# LED_RED_0603x8.net
KiCad netlist of a schematic drawn in Altium Designer
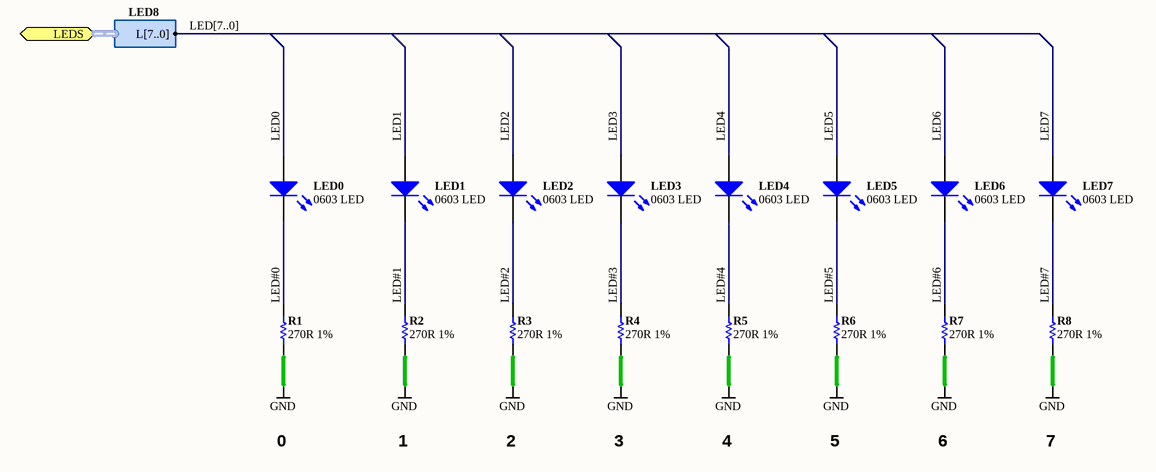
[diagram p0: LED_RED_0603x8.SCHDOC]

(export (version "E")
  (design (tool "Eeschema 10.0.6"))
  (components
    (comp (ref "LED0")
      (value "0603 LED")
      (footprint "0603LED")
      (description "LED, Red 0603 (1608) 63mCd")
      (libsource (lib "altium-import") (part "root_1_DIO-LED-1S_"))
    )
    (comp (ref "LED1")
      (value "0603 LED")
      (footprint "0603LED")
      (description "LED, Red 0603 (1608) 63mCd")
      (libsource (lib "altium-import") (part "root_1_DIO-LED-1S_"))
    )
    (comp (ref "LED2")
      (value "0603 LED")
      (footprint "0603LED")
      (description "LED, Red 0603 (1608) 63mCd")
      (libsource (lib "altium-import") (part "root_1_DIO-LED-1S_"))
    )
    (comp (ref "LED3")
      (value "0603 LED")
      (footprint "0603LED")
      (description "LED, Red 0603 (1608) 63mCd")
      (libsource (lib "altium-import") (part "root_1_DIO-LED-1S_"))
    )
    (comp (ref "LED4")
      (value "0603 LED")
      (footprint "0603LED")
      (description "LED, Red 0603 (1608) 63mCd")
      (libsource (lib "altium-import") (part "root_1_DIO-LED-1S_"))
    )
    (comp (ref "LED5")
      (value "0603 LED")
      (footprint "0603LED")
      (description "LED, Red 0603 (1608) 63mCd")
      (libsource (lib "altium-import") (part "root_1_DIO-LED-1S_"))
    )
    (comp (ref "LED6")
      (value "0603 LED")
      (footprint "0603LED")
      (description "LED, Red 0603 (1608) 63mCd")
      (libsource (lib "altium-import") (part "root_1_DIO-LED-1S_"))
    )
    (comp (ref "LED7")
      (value "0603 LED")
      (footprint "0603LED")
      (description "LED, Red 0603 (1608) 63mCd")
      (libsource (lib "altium-import") (part "root_1_DIO-LED-1S_"))
    )
    (comp (ref "R1")
      (value "270R 1%")
      (footprint "RESC1005-STAR")
      (description "Resistor, 270R 1% 0402 (1005)")
      (fields (field (name "TOLERANCE") "1 %"))
      (libsource (lib "altium-import") (part "root_2_RES_"))
    )
    (comp (ref "R2")
      (value "270R 1%")
      (footprint "RESC1005-STAR")
      (description "Resistor, 270R 1% 0402 (1005)")
      (fields (field (name "TOLERANCE") "1 %"))
      (libsource (lib "altium-import") (part "root_2_RES_"))
    )
    (comp (ref "R3")
      (value "270R 1%")
      (footprint "RESC1005-STAR")
      (description "Resistor, 270R 1% 0402 (1005)")
      (fields (field (name "TOLERANCE") "1 %"))
      (libsource (lib "altium-import") (part "root_2_RES_"))
    )
    (comp (ref "R4")
      (value "270R 1%")
      (footprint "RESC1005-STAR")
      (description "Resistor, 270R 1% 0402 (1005)")
      (fields (field (name "TOLERANCE") "1 %"))
      (libsource (lib "altium-import") (part "root_2_RES_"))
    )
    (comp (ref "R5")
      (value "270R 1%")
      (footprint "RESC1005-STAR")
      (description "Resistor, 270R 1% 0402 (1005)")
      (fields (field (name "TOLERANCE") "1 %"))
      (libsource (lib "altium-import") (part "root_2_RES_"))
    )
    (comp (ref "R6")
      (value "270R 1%")
      (footprint "RESC1005-STAR")
      (description "Resistor, 270R 1% 0402 (1005)")
      (fields (field (name "TOLERANCE") "1 %"))
      (libsource (lib "altium-import") (part "root_2_RES_"))
    )
    (comp (ref "R7")
      (value "270R 1%")
      (footprint "RESC1005-STAR")
      (description "Resistor, 270R 1% 0402 (1005)")
      (fields (field (name "TOLERANCE") "1 %"))
      (libsource (lib "altium-import") (part "root_2_RES_"))
    )
    (comp (ref "R8")
      (value "270R 1%")
      (footprint "RESC1005-STAR")
      (description "Resistor, 270R 1% 0402 (1005)")
      (fields (field (name "TOLERANCE") "1 %"))
      (libsource (lib "altium-import") (part "root_2_RES_"))
    )
  )
  (nets
    (net (code "2") (name "/LED#0") (class "Default")
      (node (ref "LED0") (pin "2") (pinfunction "K_2") (pintype "passive"))
      (node (ref "R1") (pin "2") (pinfunction "2_2") (pintype "passive"))
    )
    (net (code "3") (name "/LED#1") (class "Default")
      (node (ref "LED1") (pin "2") (pinfunction "K_2") (pintype "passive"))
      (node (ref "R2") (pin "2") (pinfunction "2_2") (pintype "passive"))
    )
    (net (code "4") (name "/LED#2") (class "Default")
      (node (ref "LED2") (pin "2") (pinfunction "K_2") (pintype "passive"))
      (node (ref "R3") (pin "2") (pinfunction "2_2") (pintype "passive"))
    )
    (net (code "5") (name "/LED#3") (class "Default")
      (node (ref "LED3") (pin "2") (pinfunction "K_2") (pintype "passive"))
      (node (ref "R4") (pin "2") (pinfunction "2_2") (pintype "passive"))
    )
    (net (code "6") (name "/LED#4") (class "Default")
      (node (ref "LED4") (pin "2") (pinfunction "K_2") (pintype "passive"))
      (node (ref "R5") (pin "2") (pinfunction "2_2") (pintype "passive"))
    )
    (net (code "7") (name "/LED#5") (class "Default")
      (node (ref "LED5") (pin "2") (pinfunction "K_2") (pintype "passive"))
      (node (ref "R6") (pin "2") (pinfunction "2_2") (pintype "passive"))
    )
    (net (code "8") (name "/LED#6") (class "Default")
      (node (ref "LED6") (pin "2") (pinfunction "K_2") (pintype "passive"))
      (node (ref "R7") (pin "2") (pinfunction "2_2") (pintype "passive"))
    )
    (net (code "9") (name "/LED#7") (class "Default")
      (node (ref "LED7") (pin "2") (pinfunction "K_2") (pintype "passive"))
      (node (ref "R8") (pin "2") (pinfunction "2_2") (pintype "passive"))
    )
    (net (code "10") (name "/LED0") (class "Default")
      (node (ref "LED0") (pin "1") (pinfunction "A_1") (pintype "passive"))
    )
    (net (code "11") (name "/LED1") (class "Default")
      (node (ref "LED1") (pin "1") (pinfunction "A_1") (pintype "passive"))
    )
    (net (code "12") (name "/LED2") (class "Default")
      (node (ref "LED2") (pin "1") (pinfunction "A_1") (pintype "passive"))
    )
    (net (code "13") (name "/LED3") (class "Default")
      (node (ref "LED3") (pin "1") (pinfunction "A_1") (pintype "passive"))
    )
    (net (code "14") (name "/LED4") (class "Default")
      (node (ref "LED4") (pin "1") (pinfunction "A_1") (pintype "passive"))
    )
    (net (code "15") (name "/LED5") (class "Default")
      (node (ref "LED5") (pin "1") (pinfunction "A_1") (pintype "passive"))
    )
    (net (code "16") (name "/LED6") (class "Default")
      (node (ref "LED6") (pin "1") (pinfunction "A_1") (pintype "passive"))
    )
    (net (code "17") (name "/LED7") (class "Default")
      (node (ref "LED7") (pin "1") (pinfunction "A_1") (pintype "passive"))
    )
    (net (code "20") (name "GND") (class "Default")
      (node (ref "R1") (pin "1") (pinfunction "1_1") (pintype "passive"))
      (node (ref "R2") (pin "1") (pinfunction "1_1") (pintype "passive"))
      (node (ref "R3") (pin "1") (pinfunction "1_1") (pintype "passive"))
      (node (ref "R4") (pin "1") (pinfunction "1_1") (pintype "passive"))
      (node (ref "R5") (pin "1") (pinfunction "1_1") (pintype "passive"))
      (node (ref "R6") (pin "1") (pinfunction "1_1") (pintype "passive"))
      (node (ref "R7") (pin "1") (pinfunction "1_1") (pintype "passive"))
      (node (ref "R8") (pin "1") (pinfunction "1_1") (pintype "passive"))
    )
  )
)
